# Pi_Observer_board_schematic.net
KiCad netlist of a schematic drawn in EAGLE
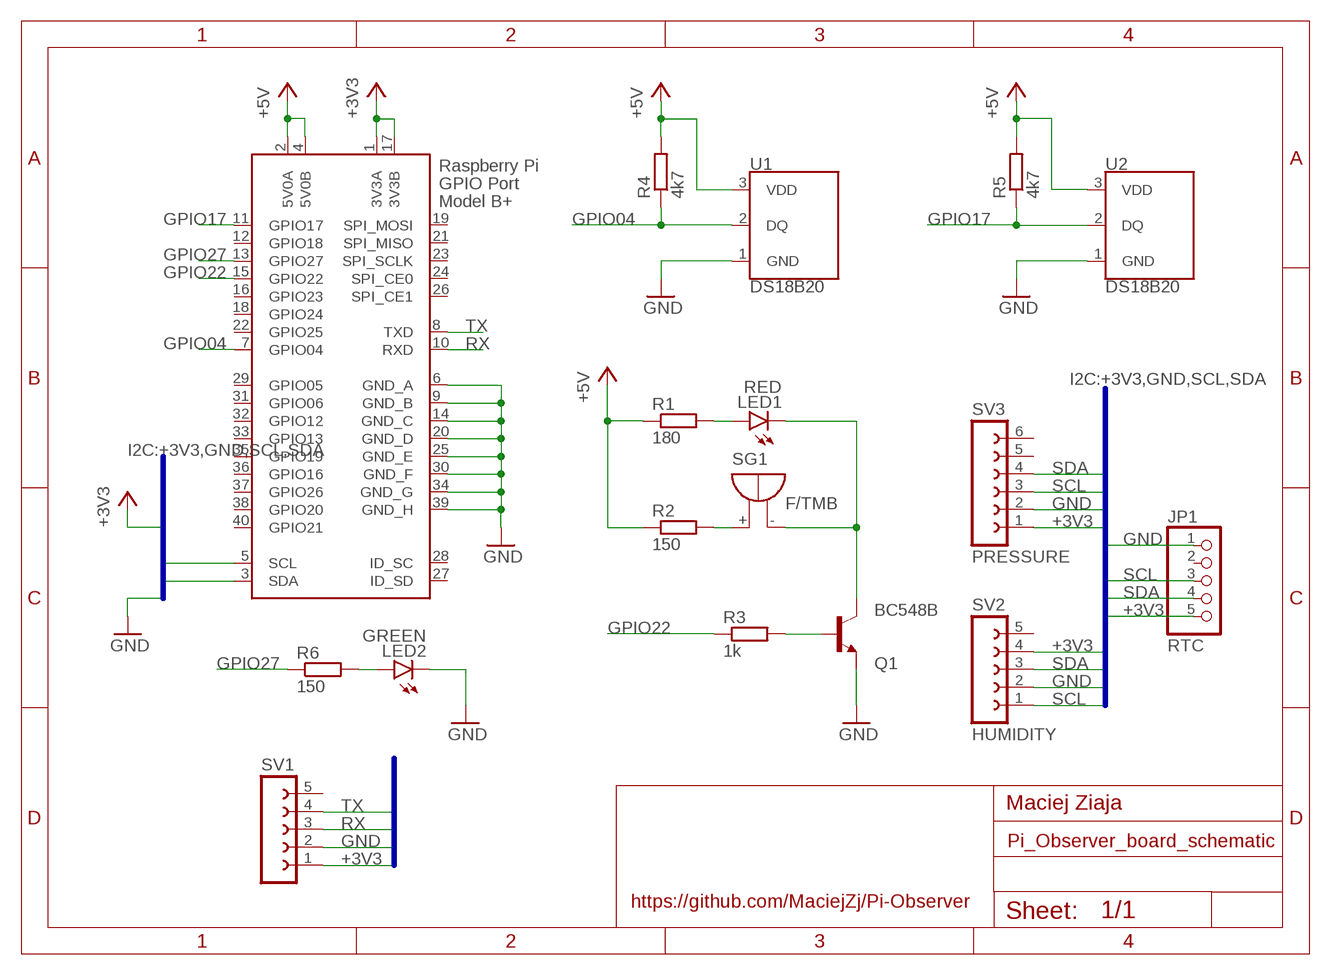
[diagram p0: schematic, sheet 1]

(export (version "E")
  (design (tool "Eeschema 10.0.6"))
  (components
    (comp (ref "JP1")
      (value "RTC")
      (footprint "eagle-import:1X05")
      (libsource (lib "eagle-import") (part "PINHD-1X5"))
    )
    (comp (ref "LED1")
      (value "RED")
      (footprint "eagle-import:LED5MM")
      (libsource (lib "eagle-import") (part "LED5MM"))
    )
    (comp (ref "LED2")
      (value "GREEN")
      (footprint "eagle-import:LED5MM")
      (libsource (lib "eagle-import") (part "LED5MM"))
    )
    (comp (ref "Q1")
      (value "BC548B")
      (footprint "eagle-import:TO92-EBC")
      (libsource (lib "eagle-import") (part "BC548B"))
    )
    (comp (ref "R1")
      (value "180")
      (footprint "eagle-import:M1206")
      (libsource (lib "eagle-import") (part "R-EU_M1206"))
    )
    (comp (ref "R2")
      (value "150")
      (footprint "eagle-import:M1206")
      (libsource (lib "eagle-import") (part "R-EU_M1206"))
    )
    (comp (ref "R3")
      (value "1k")
      (footprint "eagle-import:M1206")
      (libsource (lib "eagle-import") (part "R-EU_M1206"))
    )
    (comp (ref "R4")
      (value "4k7")
      (footprint "eagle-import:M1206")
      (libsource (lib "eagle-import") (part "R-EU_M1206"))
    )
    (comp (ref "R5")
      (value "4k7")
      (footprint "eagle-import:M1206")
      (libsource (lib "eagle-import") (part "R-EU_M1206"))
    )
    (comp (ref "R6")
      (value "150")
      (footprint "eagle-import:M1206")
      (libsource (lib "eagle-import") (part "R-EU_M1206"))
    )
    (comp (ref "SG1")
      (value "F/TMB")
      (footprint "eagle-import:F_TMB")
      (libsource (lib "eagle-import") (part "F/TMB"))
    )
    (comp (ref "SV1")
      (value "FE05-1")
      (footprint "eagle-import:FE05-1")
      (libsource (lib "eagle-import") (part "FE05-1"))
    )
    (comp (ref "SV2")
      (value "HUMIDITY")
      (footprint "eagle-import:FE05-1")
      (libsource (lib "eagle-import") (part "FE05-1"))
    )
    (comp (ref "SV3")
      (value "PRESSURE")
      (footprint "eagle-import:FE06")
      (libsource (lib "eagle-import") (part "FE06-1"))
    )
    (comp (ref "U1")
      (value "DS18B20")
      (footprint "eagle-import:TO-92-AMMO")
      (libsource (lib "eagle-import") (part "DS18B20"))
    )
    (comp (ref "U2")
      (value "DS18B20")
      (footprint "eagle-import:TO-92-AMMO")
      (libsource (lib "eagle-import") (part "DS18B20"))
    )
    (comp (ref "X1")
      (value "RASPI_GPIO_B+#_PIN")
      (footprint "eagle-import:RASPI_GPIO_B+_PIN")
      (libsource (lib "eagle-import") (part "RASPI_GPIO_B+#_PIN"))
    )
  )
  (nets
    (net (code "2") (name "+3V3") (class "Default")
      (node (ref "JP1") (pin "5") (pinfunction "5_5") (pintype "passive"))
      (node (ref "SV1") (pin "1") (pinfunction "1_1") (pintype "passive"))
      (node (ref "SV2") (pin "4") (pinfunction "4_4") (pintype "passive"))
      (node (ref "SV3") (pin "1") (pinfunction "1_1") (pintype "passive"))
      (node (ref "X1") (pin "1") (pinfunction "3V3A_1") (pintype "power_in"))
      (node (ref "X1") (pin "17") (pinfunction "3V3B_17") (pintype "power_in"))
    )
    (net (code "3") (name "+5V") (class "Default")
      (node (ref "R1") (pin "1") (pinfunction "1_1") (pintype "passive"))
      (node (ref "R2") (pin "1") (pinfunction "1_1") (pintype "passive"))
      (node (ref "R4") (pin "2") (pinfunction "2_2") (pintype "passive"))
      (node (ref "R5") (pin "2") (pinfunction "2_2") (pintype "passive"))
      (node (ref "U1") (pin "3") (pinfunction "VDD_3") (pintype "power_in"))
      (node (ref "U2") (pin "3") (pinfunction "VDD_3") (pintype "power_in"))
      (node (ref "X1") (pin "2") (pinfunction "5V0A_2") (pintype "power_in"))
      (node (ref "X1") (pin "4") (pinfunction "5V0B_4") (pintype "power_in"))
    )
    (net (code "4") (name "/GPIO04") (class "Default")
      (node (ref "R4") (pin "1") (pinfunction "1_1") (pintype "passive"))
      (node (ref "U1") (pin "2") (pinfunction "DQ_2") (pintype "bidirectional"))
      (node (ref "X1") (pin "7") (pinfunction "GPIO04_7") (pintype "bidirectional"))
    )
    (net (code "5") (name "/GPIO17") (class "Default")
      (node (ref "R5") (pin "1") (pinfunction "1_1") (pintype "passive"))
      (node (ref "U2") (pin "2") (pinfunction "DQ_2") (pintype "bidirectional"))
      (node (ref "X1") (pin "11") (pinfunction "GPIO17_11") (pintype "bidirectional"))
    )
    (net (code "6") (name "/GPIO22") (class "Default")
      (node (ref "R3") (pin "1") (pinfunction "1_1") (pintype "passive"))
      (node (ref "X1") (pin "15") (pinfunction "GPIO22_15") (pintype "bidirectional"))
    )
    (net (code "7") (name "/GPIO27") (class "Default")
      (node (ref "R6") (pin "1") (pinfunction "1_1") (pintype "passive"))
      (node (ref "X1") (pin "13") (pinfunction "GPIO27_13") (pintype "bidirectional"))
    )
    (net (code "8") (name "/RX") (class "Default")
      (node (ref "SV1") (pin "3") (pinfunction "3_3") (pintype "passive"))
      (node (ref "X1") (pin "10") (pinfunction "RXD_10") (pintype "bidirectional"))
    )
    (net (code "9") (name "/SCL") (class "Default")
      (node (ref "JP1") (pin "3") (pinfunction "3_3") (pintype "passive"))
      (node (ref "SV2") (pin "1") (pinfunction "1_1") (pintype "passive"))
      (node (ref "SV3") (pin "3") (pinfunction "3_3") (pintype "passive"))
      (node (ref "X1") (pin "5") (pinfunction "SCL_5") (pintype "bidirectional"))
    )
    (net (code "10") (name "/SDA") (class "Default")
      (node (ref "JP1") (pin "4") (pinfunction "4_4") (pintype "passive"))
      (node (ref "SV2") (pin "3") (pinfunction "3_3") (pintype "passive"))
      (node (ref "SV3") (pin "4") (pinfunction "4_4") (pintype "passive"))
      (node (ref "X1") (pin "3") (pinfunction "SDA_3") (pintype "bidirectional"))
    )
    (net (code "11") (name "/TX") (class "Default")
      (node (ref "SV1") (pin "4") (pinfunction "4_4") (pintype "passive"))
      (node (ref "X1") (pin "8") (pinfunction "TXD_8") (pintype "bidirectional"))
    )
    (net (code "13") (name "GND") (class "Default")
      (node (ref "JP1") (pin "1") (pinfunction "1_1") (pintype "passive"))
      (node (ref "LED2") (pin "K") (pinfunction "C_K") (pintype "passive"))
      (node (ref "Q1") (pin "E") (pinfunction "E_E") (pintype "passive"))
      (node (ref "SV1") (pin "2") (pinfunction "2_2") (pintype "passive"))
      (node (ref "SV2") (pin "2") (pinfunction "2_2") (pintype "passive"))
      (node (ref "SV3") (pin "2") (pinfunction "2_2") (pintype "passive"))
      (node (ref "U1") (pin "1") (pinfunction "GND_1") (pintype "power_in"))
      (node (ref "U2") (pin "1") (pinfunction "GND_1") (pintype "power_in"))
      (node (ref "X1") (pin "14") (pinfunction "GND_C_14") (pintype "power_in"))
      (node (ref "X1") (pin "20") (pinfunction "GND_D_20") (pintype "power_in"))
      (node (ref "X1") (pin "25") (pinfunction "GND_E_25") (pintype "power_in"))
      (node (ref "X1") (pin "30") (pinfunction "GND_F_30") (pintype "power_in"))
      (node (ref "X1") (pin "34") (pinfunction "GND_G_34") (pintype "power_in"))
      (node (ref "X1") (pin "39") (pinfunction "GND_H_39") (pintype "power_in"))
      (node (ref "X1") (pin "6") (pinfunction "GND_A_6") (pintype "power_in"))
      (node (ref "X1") (pin "9") (pinfunction "GND_B_9") (pintype "power_in"))
    )
    (net (code "14") (name "Net-(LED1-C)") (class "Default")
      (node (ref "LED1") (pin "K") (pinfunction "C_K") (pintype "passive"))
      (node (ref "Q1") (pin "C") (pinfunction "C_C") (pintype "passive"))
      (node (ref "SG1") (pin "-") (pinfunction "-_-") (pintype "passive"))
    )
    (net (code "15") (name "Net-(LED1-PadA)") (class "Default")
      (node (ref "LED1") (pin "A") (pinfunction "A_A") (pintype "passive"))
      (node (ref "R1") (pin "2") (pinfunction "2_2") (pintype "passive"))
    )
    (net (code "16") (name "Net-(LED2-PadA)") (class "Default")
      (node (ref "LED2") (pin "A") (pinfunction "A_A") (pintype "passive"))
      (node (ref "R6") (pin "2") (pinfunction "2_2") (pintype "passive"))
    )
    (net (code "17") (name "Net-(Q1-PadB)") (class "Default")
      (node (ref "Q1") (pin "B") (pinfunction "B_B") (pintype "passive"))
      (node (ref "R3") (pin "2") (pinfunction "2_2") (pintype "passive"))
    )
    (net (code "18") (name "Net-(R2-Pad2)") (class "Default")
      (node (ref "R2") (pin "2") (pinfunction "2_2") (pintype "passive"))
      (node (ref "SG1") (pin "+") (pinfunction "+_+") (pintype "passive"))
    )
    (net (code "19") (name "unconnected-(JP1-Pad2)") (class "Default")
      (node (ref "JP1") (pin "2") (pinfunction "2_2") (pintype "passive"))
    )
    (net (code "20") (name "unconnected-(SV1-Pad5)") (class "Default")
      (node (ref "SV1") (pin "5") (pinfunction "5_5") (pintype "passive"))
    )
    (net (code "21") (name "unconnected-(SV2-Pad5)") (class "Default")
      (node (ref "SV2") (pin "5") (pinfunction "5_5") (pintype "passive"))
    )
    (net (code "22") (name "unconnected-(SV3-Pad5)") (class "Default")
      (node (ref "SV3") (pin "5") (pinfunction "5_5") (pintype "passive"))
    )
    (net (code "23") (name "unconnected-(SV3-Pad6)") (class "Default")
      (node (ref "SV3") (pin "6") (pinfunction "6_6") (pintype "passive"))
    )
    (net (code "24") (name "unconnected-(X1-GPIO05-Pad29)") (class "Default")
      (node (ref "X1") (pin "29") (pinfunction "GPIO05_29") (pintype "no_connect"))
    )
    (net (code "25") (name "unconnected-(X1-GPIO06-Pad31)") (class "Default")
      (node (ref "X1") (pin "31") (pinfunction "GPIO06_31") (pintype "no_connect"))
    )
    (net (code "26") (name "unconnected-(X1-GPIO12-Pad32)") (class "Default")
      (node (ref "X1") (pin "32") (pinfunction "GPIO12_32") (pintype "no_connect"))
    )
    (net (code "27") (name "unconnected-(X1-GPIO13-Pad33)") (class "Default")
      (node (ref "X1") (pin "33") (pinfunction "GPIO13_33") (pintype "no_connect"))
    )
    (net (code "28") (name "unconnected-(X1-GPIO16-Pad36)") (class "Default")
      (node (ref "X1") (pin "36") (pinfunction "GPIO16_36") (pintype "no_connect"))
    )
    (net (code "29") (name "unconnected-(X1-GPIO18-Pad12)") (class "Default")
      (node (ref "X1") (pin "12") (pinfunction "GPIO18_12") (pintype "bidirectional"))
    )
    (net (code "30") (name "unconnected-(X1-GPIO19-Pad35)") (class "Default")
      (node (ref "X1") (pin "35") (pinfunction "GPIO19_35") (pintype "no_connect"))
    )
    (net (code "31") (name "unconnected-(X1-GPIO20-Pad38)") (class "Default")
      (node (ref "X1") (pin "38") (pinfunction "GPIO20_38") (pintype "no_connect"))
    )
    (net (code "32") (name "unconnected-(X1-GPIO21-Pad40)") (class "Default")
      (node (ref "X1") (pin "40") (pinfunction "GPIO21_40") (pintype "no_connect"))
    )
    (net (code "33") (name "unconnected-(X1-GPIO23-Pad16)") (class "Default")
      (node (ref "X1") (pin "16") (pinfunction "GPIO23_16") (pintype "bidirectional"))
    )
    (net (code "34") (name "unconnected-(X1-GPIO24-Pad18)") (class "Default")
      (node (ref "X1") (pin "18") (pinfunction "GPIO24_18") (pintype "bidirectional"))
    )
    (net (code "35") (name "unconnected-(X1-GPIO25-Pad22)") (class "Default")
      (node (ref "X1") (pin "22") (pinfunction "GPIO25_22") (pintype "bidirectional"))
    )
    (net (code "36") (name "unconnected-(X1-GPIO26-Pad37)") (class "Default")
      (node (ref "X1") (pin "37") (pinfunction "GPIO26_37") (pintype "no_connect"))
    )
    (net (code "37") (name "unconnected-(X1-ID_SC-Pad28)") (class "Default")
      (node (ref "X1") (pin "28") (pinfunction "ID_SC_28") (pintype "no_connect"))
    )
    (net (code "38") (name "unconnected-(X1-ID_SD-Pad27)") (class "Default")
      (node (ref "X1") (pin "27") (pinfunction "ID_SD_27") (pintype "no_connect"))
    )
    (net (code "39") (name "unconnected-(X1-SPI_CE0-Pad24)") (class "Default")
      (node (ref "X1") (pin "24") (pinfunction "SPI_CE0_24") (pintype "bidirectional"))
    )
    (net (code "40") (name "unconnected-(X1-SPI_CE1-Pad26)") (class "Default")
      (node (ref "X1") (pin "26") (pinfunction "SPI_CE1_26") (pintype "bidirectional"))
    )
    (net (code "41") (name "unconnected-(X1-SPI_MISO-Pad21)") (class "Default")
      (node (ref "X1") (pin "21") (pinfunction "SPI_MISO_21") (pintype "bidirectional"))
    )
    (net (code "42") (name "unconnected-(X1-SPI_MOSI-Pad19)") (class "Default")
      (node (ref "X1") (pin "19") (pinfunction "SPI_MOSI_19") (pintype "bidirectional"))
    )
    (net (code "43") (name "unconnected-(X1-SPI_SCLK-Pad23)") (class "Default")
      (node (ref "X1") (pin "23") (pinfunction "SPI_SCLK_23") (pintype "bidirectional"))
    )
  )
)
